# MadHaddrMkrZero.net
KiCad netlist of a schematic drawn in EAGLE
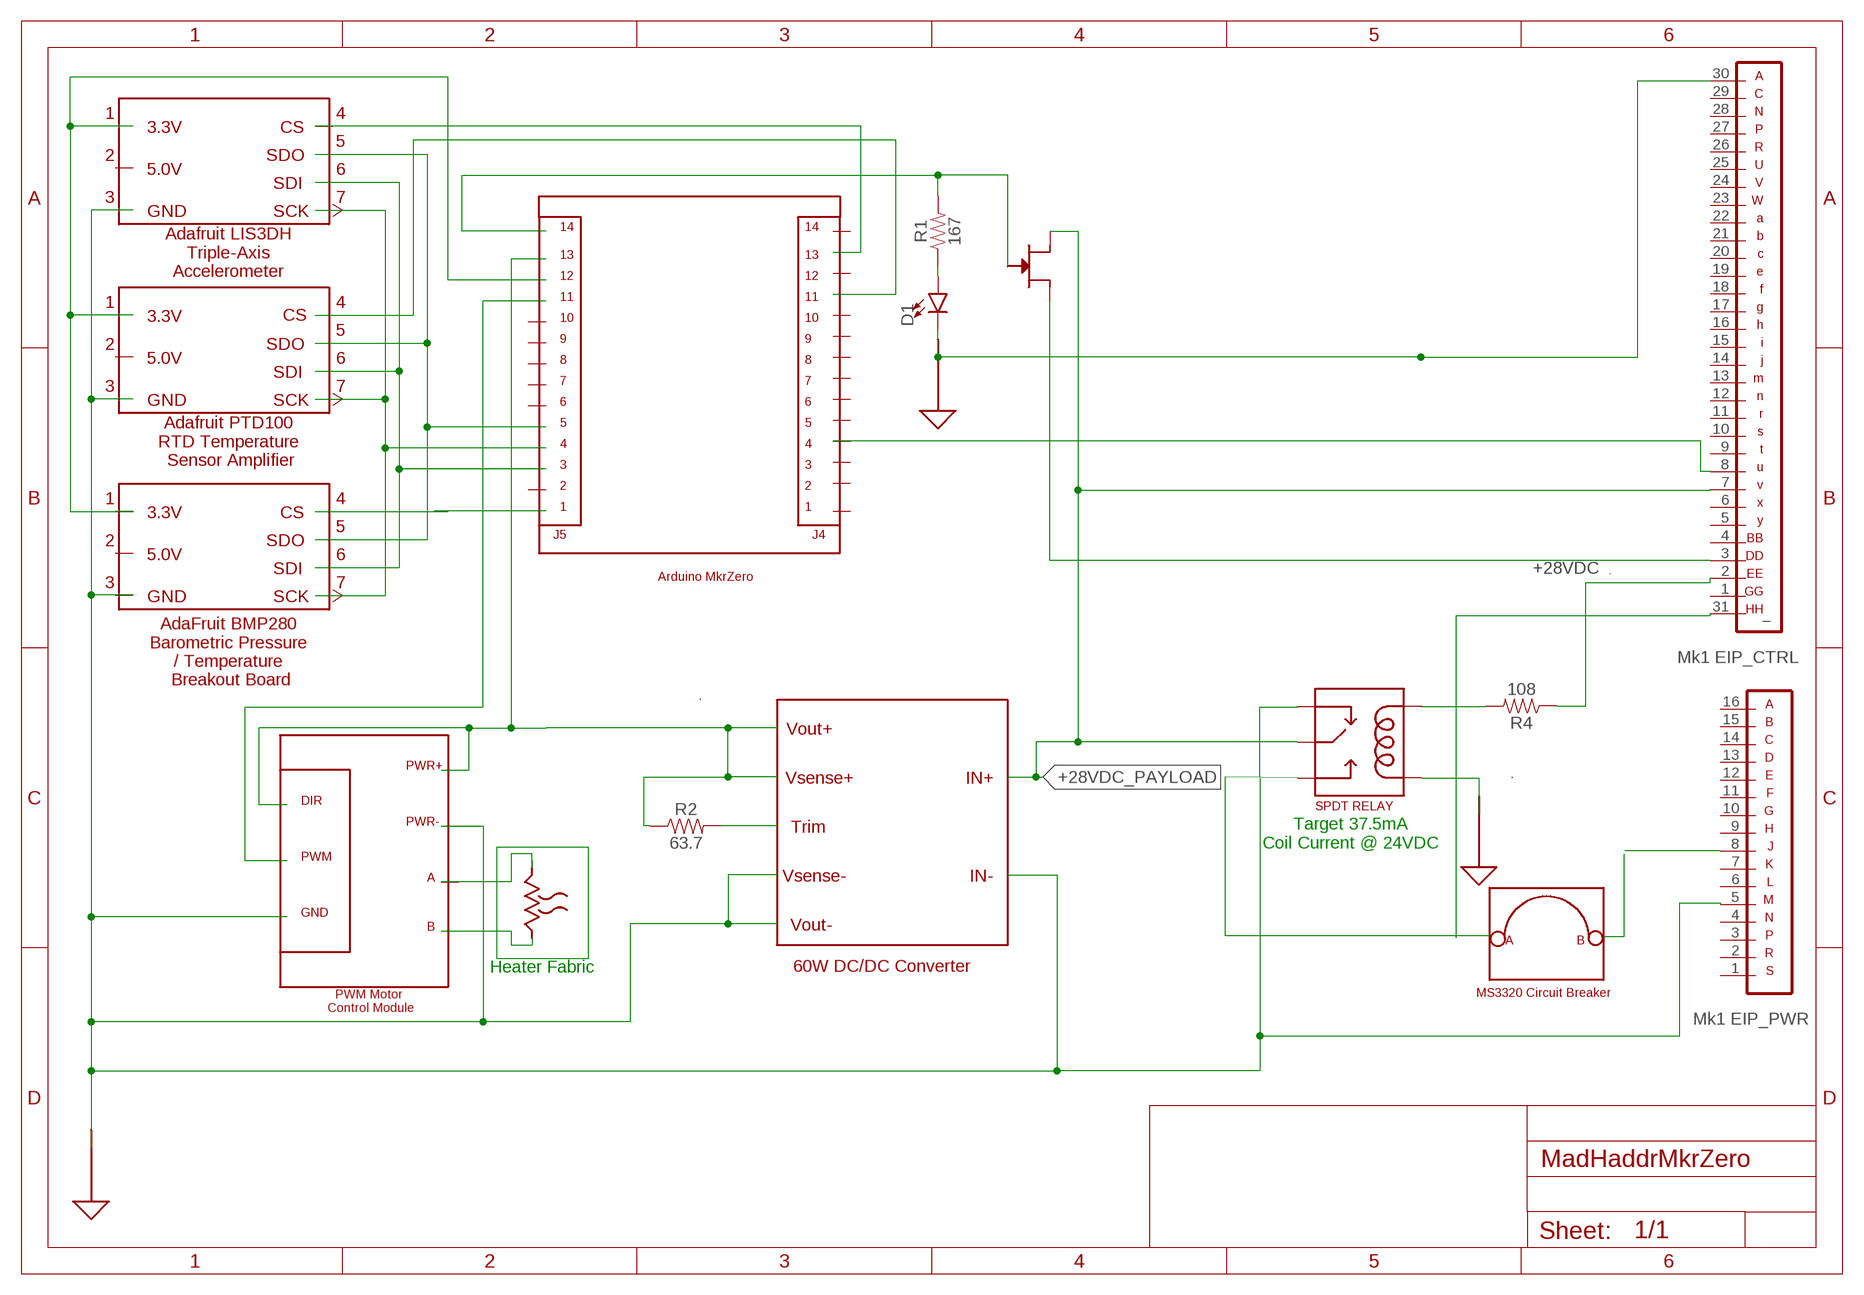
[diagram p0: schematic, sheet 1]

(export (version "E")
  (design (tool "Eeschema 10.0.6"))
  (components
    (comp (ref "D1")
      (value "LED3MM")
      (footprint "eagle-import:LED_3MM")
      (libsource (lib "eagle-import") (part "LED3MM"))
    )
    (comp (ref "J1")
      (value "SDGDSGG")
      (footprint "eagle-import:1X30")
      (libsource (lib "eagle-import") (part "SDGDSGG"))
    )
    (comp (ref "R1")
      (value "167")
      (footprint "eagle-import:1210")
      (libsource (lib "eagle-import") (part "0.1OHM-1210-1/2W-1%"))
    )
    (comp (ref "R2")
      (value "63.7")
      (footprint "eagle-import:1210")
      (libsource (lib "eagle-import") (part "0.1OHM-1210-1/2W-1%"))
    )
    (comp (ref "R4")
      (value "108")
      (footprint "eagle-import:1210")
      (libsource (lib "eagle-import") (part "0.1OHM-1210-1/2W-1%"))
    )
    (comp (ref "U$1")
      (value "28VDC_TO_5VDC_PWR_SUPPLY")
      (footprint "eagle-import:28VDC_TO_5VDC_PWR_SUPPLY")
      (libsource (lib "eagle-import") (part "28VDC_TO_5VDC_PWR_SUPPLY"))
    )
    (comp (ref "U$2")
      (value "SPI_TEMP")
      (footprint "eagle-import:SPI_TEMP")
      (libsource (lib "eagle-import") (part "SPI_TEMP"))
    )
    (comp (ref "U$3")
      (value "SPI_TEMP2")
      (footprint "eagle-import:SPI_TEMP")
      (libsource (lib "eagle-import") (part "SPI_TEMP2"))
    )
    (comp (ref "U$4")
      (value "SPI_ACCEL")
      (footprint "eagle-import:SPI_TEMP")
      (libsource (lib "eagle-import") (part "SPI_ACCEL"))
    )
    (comp (ref "U$5")
      (value "MKRZERO")
      (footprint "eagle-import:MKRZERO")
      (libsource (lib "eagle-import") (part "MKRZERO"))
    )
    (comp (ref "U$6")
      (value "GND")
      (footprint "eagle-import:GND")
      (libsource (lib "eagle-import") (part "GND"))
    )
    (comp (ref "U$7")
      (value "PWM_DRIVER")
      (footprint "eagle-import:PWM_DRIVER")
      (libsource (lib "eagle-import") (part "PWM_DRIVER"))
    )
    (comp (ref "U$8")
      (value "FET")
      (footprint "eagle-import:FET")
      (libsource (lib "eagle-import") (part "FET"))
    )
    (comp (ref "U$9")
      (value "GND")
      (footprint "eagle-import:GND")
      (libsource (lib "eagle-import") (part "GND"))
    )
    (comp (ref "U$10")
      (value "MK1_EIP_PWR")
      (footprint "eagle-import:1X16")
      (libsource (lib "eagle-import") (part "MK1_EIP_PWR"))
    )
    (comp (ref "U$11")
      (value "HEATER")
      (footprint "eagle-import:HEATER")
      (libsource (lib "eagle-import") (part "HEATER"))
    )
    (comp (ref "U$12")
      (value "BREAKER")
      (footprint "eagle-import:BREAKER")
      (libsource (lib "eagle-import") (part "BREAKER"))
    )
    (comp (ref "U$13")
      (value "SPDT_RELAY")
      (footprint "eagle-import:RELAY-JZC")
      (libsource (lib "eagle-import") (part "SPDT_RELAY"))
    )
    (comp (ref "U$14")
      (value "GND")
      (footprint "eagle-import:GND")
      (libsource (lib "eagle-import") (part "GND"))
    )
  )
  (nets
    (net (code "1") (name "+28VDC_PAYLOAD") (class "Default")
      (node (ref "J1") (pin "7") (pinfunction "7_7") (pintype "passive"))
      (node (ref "U$1") (pin "P$6") (pinfunction "P$6_P$6") (pintype "bidirectional"))
      (node (ref "U$13") (pin "3") (pinfunction "MAIN_3") (pintype "bidirectional"))
      (node (ref "U$8") (pin "P$1") (pinfunction "P$1_P$1") (pintype "bidirectional"))
    )
    (net (code "3") (name "Net-(D1-C)") (class "Default")
      (node (ref "D1") (pin "K") (pinfunction "C_K") (pintype "passive"))
      (node (ref "J1") (pin "30") (pinfunction "30_30") (pintype "passive"))
      (node (ref "U$9") (pin "P$1") (pinfunction "P$1_P$1") (pintype "bidirectional"))
    )
    (net (code "4") (name "Net-(D1-PadA)") (class "Default")
      (node (ref "D1") (pin "A") (pinfunction "A_A") (pintype "passive"))
      (node (ref "R1") (pin "1") (pinfunction "1_1") (pintype "passive"))
    )
    (net (code "5") (name "Net-(J1-Pad2)") (class "Default")
      (node (ref "J1") (pin "2") (pinfunction "2_2") (pintype "passive"))
      (node (ref "R4") (pin "1") (pinfunction "1_1") (pintype "passive"))
    )
    (net (code "6") (name "Net-(J1-Pad3)") (class "Default")
      (node (ref "J1") (pin "3") (pinfunction "3_3") (pintype "passive"))
      (node (ref "U$8") (pin "P$2") (pinfunction "P$2_P$2") (pintype "bidirectional"))
    )
    (net (code "7") (name "Net-(J1-Pad8)") (class "Default")
      (node (ref "J1") (pin "8") (pinfunction "8_8") (pintype "passive"))
      (node (ref "U$5") (pin "P$11") (pinfunction "P$11_P$11") (pintype "bidirectional"))
    )
    (net (code "8") (name "Net-(R1-Pad2)") (class "Default")
      (node (ref "R1") (pin "2") (pinfunction "2_2") (pintype "passive"))
      (node (ref "U$5") (pin "P$1") (pinfunction "P$1_P$1") (pintype "bidirectional"))
      (node (ref "U$8") (pin "P$3") (pinfunction "P$3_P$3") (pintype "bidirectional"))
    )
    (net (code "9") (name "Net-(R2-Pad1)") (class "Default")
      (node (ref "R2") (pin "1") (pinfunction "1_1") (pintype "passive"))
      (node (ref "U$1") (pin "P$1") (pinfunction "P$1_P$1") (pintype "bidirectional"))
      (node (ref "U$1") (pin "P$2") (pinfunction "P$2_P$2") (pintype "bidirectional"))
      (node (ref "U$5") (pin "P$2") (pinfunction "P$2_P$2") (pintype "bidirectional"))
      (node (ref "U$7") (pin "P$1") (pinfunction "P$1_P$1") (pintype "bidirectional"))
      (node (ref "U$7") (pin "P$4") (pinfunction "P$4_P$4") (pintype "bidirectional"))
    )
    (net (code "10") (name "Net-(R2-Pad2)") (class "Default")
      (node (ref "R2") (pin "2") (pinfunction "2_2") (pintype "passive"))
      (node (ref "U$1") (pin "P$3") (pinfunction "P$3_P$3") (pintype "bidirectional"))
    )
    (net (code "11") (name "Net-(U$2-3.3V)") (class "Default")
      (node (ref "U$2") (pin "P$1") (pinfunction "3.3V_P$1") (pintype "bidirectional"))
      (node (ref "U$3") (pin "P$1") (pinfunction "3.3V_P$1") (pintype "bidirectional"))
      (node (ref "U$4") (pin "P$1") (pinfunction "3.3V_P$1") (pintype "bidirectional"))
      (node (ref "U$5") (pin "P$4") (pinfunction "P$4_P$4") (pintype "bidirectional"))
    )
    (net (code "12") (name "Net-(U$2-CS_5V)") (class "Default")
      (node (ref "U$2") (pin "P$3") (pinfunction "CS_5V_P$3") (pintype "bidirectional"))
      (node (ref "U$3") (pin "P$3") (pinfunction "CS_5V_P$3") (pintype "bidirectional"))
      (node (ref "U$4") (pin "P$3") (pinfunction "CS_5V_P$3") (pintype "bidirectional"))
      (node (ref "U$5") (pin "P$5") (pinfunction "P$5_P$5") (pintype "bidirectional"))
    )
    (net (code "13") (name "Net-(U$2-GND)") (class "Default")
      (node (ref "U$1") (pin "P$4") (pinfunction "P$4_P$4") (pintype "bidirectional"))
      (node (ref "U$1") (pin "P$5") (pinfunction "P$5_P$5") (pintype "bidirectional"))
      (node (ref "U$1") (pin "P$7") (pinfunction "P$7_P$7") (pintype "bidirectional"))
      (node (ref "U$10") (pin "5") (pinfunction "5_5") (pintype "passive"))
      (node (ref "U$2") (pin "P$4") (pinfunction "GND_P$4") (pintype "bidirectional"))
      (node (ref "U$3") (pin "P$4") (pinfunction "GND_P$4") (pintype "bidirectional"))
      (node (ref "U$4") (pin "P$4") (pinfunction "GND_P$4") (pintype "bidirectional"))
      (node (ref "U$6") (pin "P$1") (pinfunction "P$1_P$1") (pintype "bidirectional"))
      (node (ref "U$7") (pin "P$3") (pinfunction "P$3_P$3") (pintype "bidirectional"))
      (node (ref "U$7") (pin "P$5") (pinfunction "P$5_P$5") (pintype "bidirectional"))
    )
    (net (code "14") (name "Net-(U$2-SCK{slash}SCL_5V)") (class "Default")
      (node (ref "U$2") (pin "P$5") (pinfunction "SCK/SCL_5V_P$5") (pintype "bidirectional"))
      (node (ref "U$5") (pin "P$8") (pinfunction "P$8_P$8") (pintype "bidirectional"))
    )
    (net (code "15") (name "Net-(U$2-SDI{slash}SDA_5V)") (class "Default")
      (node (ref "U$2") (pin "P$6") (pinfunction "SDI/SDA_5V_P$6") (pintype "bidirectional"))
      (node (ref "U$3") (pin "P$6") (pinfunction "SDI/SDA_5V_P$6") (pintype "bidirectional"))
      (node (ref "U$4") (pin "P$6") (pinfunction "SDI/SDA_5V_P$6") (pintype "bidirectional"))
      (node (ref "U$5") (pin "P$6") (pinfunction "P$6_P$6") (pintype "bidirectional"))
    )
    (net (code "16") (name "Net-(U$2-SDO{slash}ADR_3V)") (class "Default")
      (node (ref "U$2") (pin "P$7") (pinfunction "SDO/ADR_3V_P$7") (pintype "bidirectional"))
      (node (ref "U$3") (pin "P$7") (pinfunction "SDO/ADR_3V_P$7") (pintype "bidirectional"))
      (node (ref "U$4") (pin "P$7") (pinfunction "SDO/ADR_3V_P$7") (pintype "bidirectional"))
      (node (ref "U$5") (pin "P$18") (pinfunction "P$18_P$18") (pintype "bidirectional"))
    )
    (net (code "17") (name "Net-(U$3-SCK{slash}SCL_5V)") (class "Default")
      (node (ref "U$3") (pin "P$5") (pinfunction "SCK/SCL_5V_P$5") (pintype "bidirectional"))
      (node (ref "U$5") (pin "P$25") (pinfunction "P$25_P$25") (pintype "bidirectional"))
    )
    (net (code "18") (name "Net-(U$4-SCK{slash}SCL_5V)") (class "Default")
      (node (ref "U$4") (pin "P$5") (pinfunction "SCK/SCL_5V_P$5") (pintype "bidirectional"))
      (node (ref "U$5") (pin "P$27") (pinfunction "P$27_P$27") (pintype "bidirectional"))
    )
    (net (code "19") (name "Net-(U$5-PadP$3)") (class "Default")
      (node (ref "U$5") (pin "P$3") (pinfunction "P$3_P$3") (pintype "bidirectional"))
      (node (ref "U$7") (pin "P$2") (pinfunction "P$2_P$2") (pintype "bidirectional"))
    )
    (net (code "20") (name "Net-(U$11-PadP$1)") (class "Default")
      (node (ref "U$11") (pin "P$1") (pinfunction "P$1_P$1") (pintype "bidirectional"))
      (node (ref "U$7") (pin "P$7") (pinfunction "P$7_P$7") (pintype "bidirectional"))
    )
    (net (code "21") (name "Net-(U$11-PadP$2)") (class "Default")
      (node (ref "U$11") (pin "P$2") (pinfunction "P$2_P$2") (pintype "bidirectional"))
      (node (ref "U$7") (pin "P$6") (pinfunction "P$6_P$6") (pintype "bidirectional"))
    )
    (net (code "22") (name "Net-(U$13-COIL1)") (class "Default")
      (node (ref "R4") (pin "2") (pinfunction "2_2") (pintype "passive"))
      (node (ref "U$13") (pin "1") (pinfunction "COIL1_1") (pintype "bidirectional"))
    )
    (net (code "23") (name "Net-(U$13-COIL2)") (class "Default")
      (node (ref "U$13") (pin "2") (pinfunction "COIL2_2") (pintype "bidirectional"))
      (node (ref "U$14") (pin "P$1") (pinfunction "P$1_P$1") (pintype "bidirectional"))
    )
    (net (code "24") (name "Net-(U$13-NO)") (class "Default")
      (node (ref "U$12") (pin "P$2") (pinfunction "P$2_P$2") (pintype "bidirectional"))
      (node (ref "U$13") (pin "5") (pinfunction "NO_5") (pintype "bidirectional"))
    )
    (net (code "25") (name "unconnected-(J1-Pad1)") (class "Default")
      (node (ref "J1") (pin "1") (pinfunction "1_1") (pintype "passive"))
    )
    (net (code "26") (name "unconnected-(J1-Pad4)") (class "Default")
      (node (ref "J1") (pin "4") (pinfunction "4_4") (pintype "passive"))
    )
    (net (code "27") (name "unconnected-(J1-Pad5)") (class "Default")
      (node (ref "J1") (pin "5") (pinfunction "5_5") (pintype "passive"))
    )
    (net (code "28") (name "unconnected-(J1-Pad6)") (class "Default")
      (node (ref "J1") (pin "6") (pinfunction "6_6") (pintype "passive"))
    )
    (net (code "29") (name "unconnected-(J1-Pad9)") (class "Default")
      (node (ref "J1") (pin "9") (pinfunction "9_9") (pintype "passive"))
    )
    (net (code "30") (name "unconnected-(J1-Pad10)") (class "Default")
      (node (ref "J1") (pin "10") (pinfunction "10_10") (pintype "passive"))
    )
    (net (code "31") (name "unconnected-(J1-Pad11)") (class "Default")
      (node (ref "J1") (pin "11") (pinfunction "11_11") (pintype "passive"))
    )
    (net (code "32") (name "unconnected-(J1-Pad12)") (class "Default")
      (node (ref "J1") (pin "12") (pinfunction "12_12") (pintype "passive"))
    )
    (net (code "33") (name "unconnected-(J1-Pad13)") (class "Default")
      (node (ref "J1") (pin "13") (pinfunction "13_13") (pintype "passive"))
    )
    (net (code "34") (name "unconnected-(J1-Pad14)") (class "Default")
      (node (ref "J1") (pin "14") (pinfunction "14_14") (pintype "passive"))
    )
    (net (code "35") (name "unconnected-(J1-Pad15)") (class "Default")
      (node (ref "J1") (pin "15") (pinfunction "15_15") (pintype "passive"))
    )
    (net (code "36") (name "unconnected-(J1-Pad16)") (class "Default")
      (node (ref "J1") (pin "16") (pinfunction "16_16") (pintype "passive"))
    )
    (net (code "37") (name "unconnected-(J1-Pad17)") (class "Default")
      (node (ref "J1") (pin "17") (pinfunction "17_17") (pintype "passive"))
    )
    (net (code "38") (name "unconnected-(J1-Pad18)") (class "Default")
      (node (ref "J1") (pin "18") (pinfunction "18_18") (pintype "passive"))
    )
    (net (code "39") (name "unconnected-(J1-Pad19)") (class "Default")
      (node (ref "J1") (pin "19") (pinfunction "19_19") (pintype "passive"))
    )
    (net (code "40") (name "unconnected-(J1-Pad20)") (class "Default")
      (node (ref "J1") (pin "20") (pinfunction "20_20") (pintype "passive"))
    )
    (net (code "41") (name "unconnected-(J1-Pad21)") (class "Default")
      (node (ref "J1") (pin "21") (pinfunction "21_21") (pintype "passive"))
    )
    (net (code "42") (name "unconnected-(J1-Pad22)") (class "Default")
      (node (ref "J1") (pin "22") (pinfunction "22_22") (pintype "passive"))
    )
    (net (code "43") (name "unconnected-(J1-Pad23)") (class "Default")
      (node (ref "J1") (pin "23") (pinfunction "23_23") (pintype "passive"))
    )
    (net (code "44") (name "unconnected-(J1-Pad24)") (class "Default")
      (node (ref "J1") (pin "24") (pinfunction "24_24") (pintype "passive"))
    )
    (net (code "45") (name "unconnected-(J1-Pad25)") (class "Default")
      (node (ref "J1") (pin "25") (pinfunction "25_25") (pintype "passive"))
    )
    (net (code "46") (name "unconnected-(J1-Pad26)") (class "Default")
      (node (ref "J1") (pin "26") (pinfunction "26_26") (pintype "passive"))
    )
    (net (code "47") (name "unconnected-(J1-Pad27)") (class "Default")
      (node (ref "J1") (pin "27") (pinfunction "27_27") (pintype "passive"))
    )
    (net (code "48") (name "unconnected-(J1-Pad28)") (class "Default")
      (node (ref "J1") (pin "28") (pinfunction "28_28") (pintype "passive"))
    )
    (net (code "49") (name "unconnected-(J1-Pad29)") (class "Default")
      (node (ref "J1") (pin "29") (pinfunction "29_29") (pintype "passive"))
    )
    (net (code "50") (name "unconnected-(J1-_-Pad31)") (class "Default")
      (node (ref "J1") (pin "31") (pinfunction "__31") (pintype "passive"))
    )
    (net (code "51") (name "unconnected-(U$2-5.0V-PadP$2)") (class "Default")
      (node (ref "U$2") (pin "P$2") (pinfunction "5.0V_P$2") (pintype "bidirectional"))
    )
    (net (code "52") (name "unconnected-(U$3-5.0V-PadP$2)") (class "Default")
      (node (ref "U$3") (pin "P$2") (pinfunction "5.0V_P$2") (pintype "bidirectional"))
    )
    (net (code "53") (name "unconnected-(U$4-5.0V-PadP$2)") (class "Default")
      (node (ref "U$4") (pin "P$2") (pinfunction "5.0V_P$2") (pintype "bidirectional"))
    )
    (net (code "54") (name "unconnected-(U$5-PadP$7)") (class "Default")
      (node (ref "U$5") (pin "P$7") (pinfunction "P$7_P$7") (pintype "bidirectional"))
    )
    (net (code "55") (name "unconnected-(U$5-PadP$9)") (class "Default")
      (node (ref "U$5") (pin "P$9") (pinfunction "P$9_P$9") (pintype "bidirectional"))
    )
    (net (code "56") (name "unconnected-(U$5-PadP$10)") (class "Default")
      (node (ref "U$5") (pin "P$10") (pinfunction "P$10_P$10") (pintype "bidirectional"))
    )
    (net (code "57") (name "unconnected-(U$5-PadP$12)") (class "Default")
      (node (ref "U$5") (pin "P$12") (pinfunction "P$12_P$12") (pintype "bidirectional"))
    )
    (net (code "58") (name "unconnected-(U$5-PadP$13)") (class "Default")
      (node (ref "U$5") (pin "P$13") (pinfunction "P$13_P$13") (pintype "bidirectional"))
    )
    (net (code "59") (name "unconnected-(U$5-PadP$14)") (class "Default")
      (node (ref "U$5") (pin "P$14") (pinfunction "P$14_P$14") (pintype "bidirectional"))
    )
    (net (code "60") (name "unconnected-(U$5-PadP$15)") (class "Default")
      (node (ref "U$5") (pin "P$15") (pinfunction "P$15_P$15") (pintype "bidirectional"))
    )
    (net (code "61") (name "unconnected-(U$5-PadP$16)") (class "Default")
      (node (ref "U$5") (pin "P$16") (pinfunction "P$16_P$16") (pintype "bidirectional"))
    )
    (net (code "62") (name "unconnected-(U$5-PadP$17)") (class "Default")
      (node (ref "U$5") (pin "P$17") (pinfunction "P$17_P$17") (pintype "bidirectional"))
    )
    (net (code "63") (name "unconnected-(U$5-PadP$19)") (class "Default")
      (node (ref "U$5") (pin "P$19") (pinfunction "P$19_P$19") (pintype "bidirectional"))
    )
    (net (code "64") (name "unconnected-(U$5-PadP$20)") (class "Default")
      (node (ref "U$5") (pin "P$20") (pinfunction "P$20_P$20") (pintype "bidirectional"))
    )
    (net (code "65") (name "unconnected-(U$5-PadP$21)") (class "Default")
      (node (ref "U$5") (pin "P$21") (pinfunction "P$21_P$21") (pintype "bidirectional"))
    )
    (net (code "66") (name "unconnected-(U$5-PadP$22)") (class "Default")
      (node (ref "U$5") (pin "P$22") (pinfunction "P$22_P$22") (pintype "bidirectional"))
    )
    (net (code "67") (name "unconnected-(U$5-PadP$23)") (class "Default")
      (node (ref "U$5") (pin "P$23") (pinfunction "P$23_P$23") (pintype "bidirectional"))
    )
    (net (code "68") (name "unconnected-(U$5-PadP$24)") (class "Default")
      (node (ref "U$5") (pin "P$24") (pinfunction "P$24_P$24") (pintype "bidirectional"))
    )
    (net (code "69") (name "unconnected-(U$5-PadP$26)") (class "Default")
      (node (ref "U$5") (pin "P$26") (pinfunction "P$26_P$26") (pintype "bidirectional"))
    )
    (net (code "70") (name "unconnected-(U$5-PadP$28)") (class "Default")
      (node (ref "U$5") (pin "P$28") (pinfunction "P$28_P$28") (pintype "bidirectional"))
    )
    (net (code "71") (name "unconnected-(U$10-Pad1)") (class "Default")
      (node (ref "U$10") (pin "1") (pinfunction "1_1") (pintype "passive"))
    )
    (net (code "72") (name "unconnected-(U$10-Pad2)") (class "Default")
      (node (ref "U$10") (pin "2") (pinfunction "2_2") (pintype "passive"))
    )
    (net (code "73") (name "unconnected-(U$10-Pad3)") (class "Default")
      (node (ref "U$10") (pin "3") (pinfunction "3_3") (pintype "passive"))
    )
    (net (code "74") (name "unconnected-(U$10-Pad4)") (class "Default")
      (node (ref "U$10") (pin "4") (pinfunction "4_4") (pintype "passive"))
    )
    (net (code "75") (name "unconnected-(U$10-Pad6)") (class "Default")
      (node (ref "U$10") (pin "6") (pinfunction "6_6") (pintype "passive"))
    )
    (net (code "76") (name "unconnected-(U$10-Pad7)") (class "Default")
      (node (ref "U$10") (pin "7") (pinfunction "7_7") (pintype "passive"))
    )
    (net (code "77") (name "unconnected-(U$10-Pad8)") (class "Default")
      (node (ref "U$10") (pin "8") (pinfunction "8_8") (pintype "passive"))
    )
    (net (code "78") (name "unconnected-(U$10-Pad9)") (class "Default")
      (node (ref "U$10") (pin "9") (pinfunction "9_9") (pintype "passive"))
    )
    (net (code "79") (name "unconnected-(U$10-Pad10)") (class "Default")
      (node (ref "U$10") (pin "10") (pinfunction "10_10") (pintype "passive"))
    )
    (net (code "80") (name "unconnected-(U$10-Pad11)") (class "Default")
      (node (ref "U$10") (pin "11") (pinfunction "11_11") (pintype "passive"))
    )
    (net (code "81") (name "unconnected-(U$10-Pad12)") (class "Default")
      (node (ref "U$10") (pin "12") (pinfunction "12_12") (pintype "passive"))
    )
    (net (code "82") (name "unconnected-(U$10-Pad13)") (class "Default")
      (node (ref "U$10") (pin "13") (pinfunction "13_13") (pintype "passive"))
    )
    (net (code "83") (name "unconnected-(U$10-Pad14)") (class "Default")
      (node (ref "U$10") (pin "14") (pinfunction "14_14") (pintype "passive"))
    )
    (net (code "84") (name "unconnected-(U$10-Pad15)") (class "Default")
      (node (ref "U$10") (pin "15") (pinfunction "15_15") (pintype "passive"))
    )
    (net (code "85") (name "unconnected-(U$10-Pad16)") (class "Default")
      (node (ref "U$10") (pin "16") (pinfunction "16_16") (pintype "passive"))
    )
    (net (code "86") (name "unconnected-(U$12-PadP$1)") (class "Default")
      (node (ref "U$12") (pin "P$1") (pinfunction "P$1_P$1") (pintype "bidirectional"))
    )
    (net (code "87") (name "unconnected-(U$13-NC-Pad4)") (class "Default")
      (node (ref "U$13") (pin "4") (pinfunction "NC_4") (pintype "bidirectional"))
    )
  )
)
